# USB_Block.net
KiCad netlist of a schematic drawn in Altium Designer
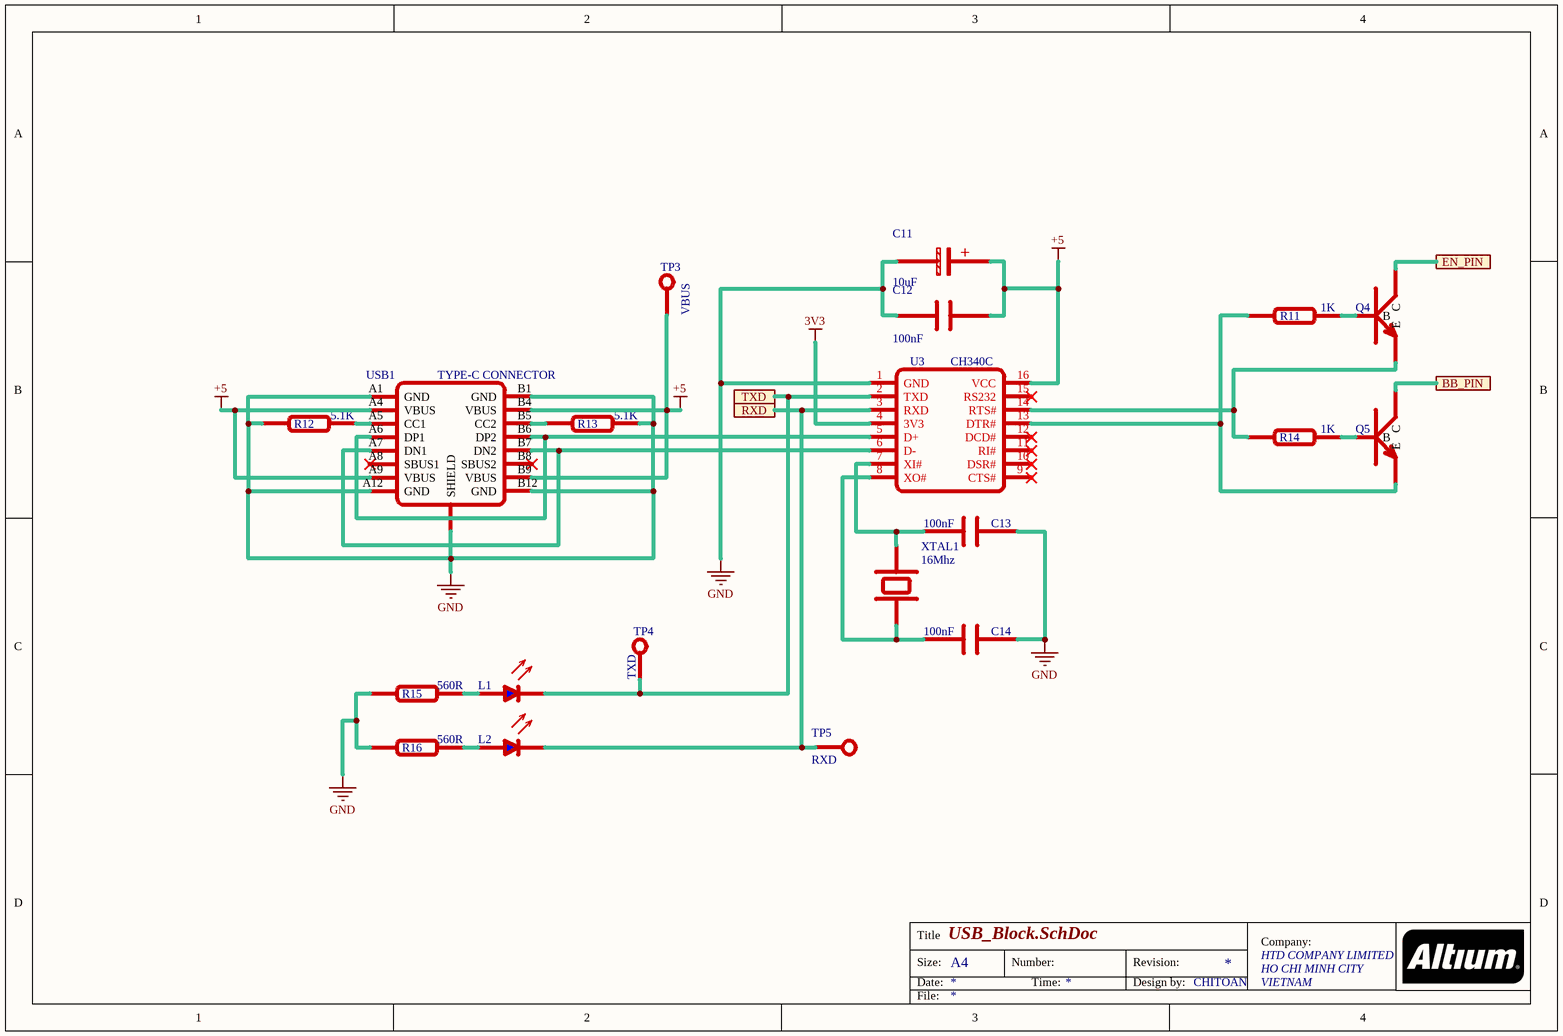
[diagram p0: USB_Block.SchDoc]

(export (version "E")
  (design (tool "Eeschema 10.0.6"))
  (components
    (comp (ref "C11")
      (value "10uF")
      (footprint "CAP-AL-4x5.4")
      (description "Aluminum Capacitor")
      (libsource (lib "CTAI-Library") (part "CAP-ALU"))
    )
    (comp (ref "C12")
      (value "100nF")
      (footprint "C0805")
      (description "Ceramic Capacitor")
      (libsource (lib "CTAI-Library") (part "CAP-CER"))
    )
    (comp (ref "C13")
      (value "100nF")
      (footprint "C0805")
      (description "Ceramic Capacitor")
      (libsource (lib "CTAI-Library") (part "CAP-CER"))
    )
    (comp (ref "C14")
      (value "100nF")
      (footprint "C0805")
      (description "Ceramic Capacitor")
      (libsource (lib "CTAI-Library") (part "CAP-CER"))
    )
    (comp (ref "L1")
      (value "LED-BLUE")
      (footprint "LED-0603-BLUE")
      (description "Blue Light Emiter Diode")
      (libsource (lib "CTAI-Library") (part "LED-Blue"))
    )
    (comp (ref "L2")
      (value "LED-BLUE")
      (footprint "LED-0603-BLUE")
      (description "Blue Light Emiter Diode")
      (libsource (lib "CTAI-Library") (part "LED-Blue"))
    )
    (comp (ref "Q4")
      (value "S8050")
      (footprint "SOT-23")
      (description "NPN Transistors 0.5A Collector to Emitter 25V")
      (libsource (lib "CTAI-Library") (part "S8050"))
    )
    (comp (ref "Q5")
      (value "S8050")
      (footprint "SOT-23")
      (description "NPN Transistors 0.5A Collector to Emitter 25V")
      (libsource (lib "CTAI-Library") (part "S8050"))
    )
    (comp (ref "R11")
      (value "1K")
      (footprint "R0603")
      (description "Resistor")
      (libsource (lib "CTAI-Library") (part "Resistor"))
    )
    (comp (ref "R12")
      (value "5.1K")
      (footprint "R0603")
      (description "Resistor")
      (libsource (lib "CTAI-Library") (part "Resistor"))
    )
    (comp (ref "R13")
      (value "5.1K")
      (footprint "R0603")
      (description "Resistor")
      (libsource (lib "CTAI-Library") (part "Resistor"))
    )
    (comp (ref "R14")
      (value "1K")
      (footprint "R0603")
      (description "Resistor")
      (libsource (lib "CTAI-Library") (part "Resistor"))
    )
    (comp (ref "R15")
      (value "560R")
      (footprint "R0603")
      (description "Resistor")
      (libsource (lib "CTAI-Library") (part "Resistor"))
    )
    (comp (ref "R16")
      (value "560R")
      (footprint "R0603")
      (description "Resistor")
      (libsource (lib "CTAI-Library") (part "Resistor"))
    )
    (comp (ref "TP3")
      (value "VBUS")
      (footprint "Test Point")
      (description "Test Point")
      (libsource (lib "CTAI-Library") (part "TestPoint"))
    )
    (comp (ref "TP4")
      (value "TXD")
      (footprint "Test Point")
      (description "Test Point")
      (libsource (lib "CTAI-Library") (part "TestPoint"))
    )
    (comp (ref "TP5")
      (value "RXD")
      (footprint "Test Point")
      (description "Test Point")
      (libsource (lib "CTAI-Library") (part "TestPoint"))
    )
    (comp (ref "U3")
      (value "CH340C")
      (footprint "SOP-16")
      (description "USB to UART bridge\r\nCH340-G-C-B")
      (libsource (lib "CTAI-Library") (part "CH340-16P"))
    )
    (comp (ref "USB1")
      (value "TYPE-C CONNECTOR")
      (footprint "USB-C-H-K-16P")
      (description "16P USB TYPE-C CONNECTOR")
      (libsource (lib "CTAI-Library") (part "USB-C-F-16P"))
    )
    (comp (ref "XTAL1")
      (value "16Mhz")
      (footprint "Crystal 5032")
      (description "Crystall 3Pin Capacitor Intergrated")
      (libsource (lib "CTAI-Library") (part "CRYSTAL-4P"))
    )
  )
  (nets
    (net (code "1") (name "+5") (class "Default")
      (node (ref "C11") (pin "1") (pintype "passive"))
      (node (ref "C12") (pin "2") (pintype "passive"))
      (node (ref "TP3") (pin "1") (pinfunction "1_1") (pintype "passive"))
      (node (ref "U3") (pin "16") (pinfunction "VCC_16") (pintype "passive"))
      (node (ref "USB1") (pin "A4") (pinfunction "VBUS_A4") (pintype "passive"))
      (node (ref "USB1") (pin "A9") (pinfunction "VBUS_A9") (pintype "passive"))
      (node (ref "USB1") (pin "B4") (pinfunction "VBUS_B4") (pintype "passive"))
      (node (ref "USB1") (pin "B9") (pinfunction "VBUS_B9") (pintype "passive"))
    )
    (net (code "2") (name "/BB_PIN") (class "Default")
      (node (ref "Q5") (pin "3") (pinfunction "C_3") (pintype "passive"))
    )
    (net (code "3") (name "/EN_PIN") (class "Default")
      (node (ref "Q4") (pin "3") (pinfunction "C_3") (pintype "passive"))
    )
    (net (code "4") (name "/RXD") (class "Default")
      (node (ref "L2") (pin "2") (pinfunction "K_2") (pintype "passive"))
      (node (ref "TP5") (pin "1") (pinfunction "1_1") (pintype "passive"))
      (node (ref "U3") (pin "3") (pinfunction "RXD_3") (pintype "passive"))
    )
    (net (code "5") (name "/TXD") (class "Default")
      (node (ref "L1") (pin "2") (pinfunction "K_2") (pintype "passive"))
      (node (ref "TP4") (pin "1") (pinfunction "1_1") (pintype "passive"))
      (node (ref "U3") (pin "2") (pinfunction "TXD_2") (pintype "passive"))
    )
    (net (code "6") (name "3V3") (class "Default")
      (node (ref "U3") (pin "4") (pinfunction "3V3_4") (pintype "passive"))
    )
    (net (code "7") (name "GND") (class "Default")
      (node (ref "C11") (pin "2") (pintype "passive"))
      (node (ref "C12") (pin "1") (pintype "passive"))
      (node (ref "C13") (pin "1") (pintype "passive"))
      (node (ref "C14") (pin "1") (pintype "passive"))
      (node (ref "R12") (pin "2") (pinfunction "2_2") (pintype "passive"))
      (node (ref "R13") (pin "1") (pinfunction "1_1") (pintype "passive"))
      (node (ref "R15") (pin "1") (pinfunction "1_1") (pintype "passive"))
      (node (ref "R16") (pin "1") (pinfunction "1_1") (pintype "passive"))
      (node (ref "U3") (pin "1") (pinfunction "GND_1") (pintype "passive"))
      (node (ref "USB1") (pin "0") (pinfunction "SHIELD_0") (pintype "passive"))
      (node (ref "USB1") (pin "A1") (pinfunction "GND_A1") (pintype "passive"))
      (node (ref "USB1") (pin "A12") (pinfunction "GND_A12") (pintype "passive"))
      (node (ref "USB1") (pin "B1") (pinfunction "GND_B1") (pintype "passive"))
      (node (ref "USB1") (pin "B12") (pinfunction "GND_B12") (pintype "passive"))
    )
    (net (code "8") (name "Net-(L1-A)") (class "Default")
      (node (ref "L1") (pin "1") (pinfunction "A_1") (pintype "passive"))
      (node (ref "R15") (pin "2") (pinfunction "2_2") (pintype "passive"))
    )
    (net (code "9") (name "Net-(L2-A)") (class "Default")
      (node (ref "L2") (pin "1") (pinfunction "A_1") (pintype "passive"))
      (node (ref "R16") (pin "2") (pinfunction "2_2") (pintype "passive"))
    )
    (net (code "10") (name "Net-(Q4-B)") (class "Default")
      (node (ref "Q4") (pin "1") (pinfunction "B_1") (pintype "passive"))
      (node (ref "R11") (pin "2") (pinfunction "2_2") (pintype "passive"))
    )
    (net (code "11") (name "Net-(Q4-E)") (class "Default")
      (node (ref "Q4") (pin "2") (pinfunction "E_2") (pintype "passive"))
      (node (ref "R14") (pin "1") (pinfunction "1_1") (pintype "passive"))
      (node (ref "U3") (pin "14") (pinfunction "RTS#_14") (pintype "passive"))
    )
    (net (code "12") (name "Net-(Q5-B)") (class "Default")
      (node (ref "Q5") (pin "1") (pinfunction "B_1") (pintype "passive"))
      (node (ref "R14") (pin "2") (pinfunction "2_2") (pintype "passive"))
    )
    (net (code "13") (name "Net-(Q5-E)") (class "Default")
      (node (ref "Q5") (pin "2") (pinfunction "E_2") (pintype "passive"))
      (node (ref "R11") (pin "1") (pinfunction "1_1") (pintype "passive"))
      (node (ref "U3") (pin "13") (pinfunction "DTR#_13") (pintype "passive"))
    )
    (net (code "14") (name "Net-(U3-D+)") (class "Default")
      (node (ref "U3") (pin "5") (pinfunction "D+_5") (pintype "passive"))
      (node (ref "USB1") (pin "A6") (pinfunction "DP1_A6") (pintype "passive"))
      (node (ref "USB1") (pin "B6") (pinfunction "DP2_B6") (pintype "passive"))
    )
    (net (code "15") (name "Net-(U3-D-)") (class "Default")
      (node (ref "U3") (pin "6") (pinfunction "D-_6") (pintype "passive"))
      (node (ref "USB1") (pin "A7") (pinfunction "DN1_A7") (pintype "passive"))
      (node (ref "USB1") (pin "B7") (pinfunction "DN2_B7") (pintype "passive"))
    )
    (net (code "16") (name "Net-(U3-XI#)") (class "Default")
      (node (ref "C13") (pin "2") (pintype "passive"))
      (node (ref "U3") (pin "7") (pinfunction "XI#_7") (pintype "passive"))
      (node (ref "XTAL1") (pin "1") (pintype "passive"))
    )
    (net (code "17") (name "Net-(U3-XO#)") (class "Default")
      (node (ref "C14") (pin "2") (pintype "passive"))
      (node (ref "U3") (pin "8") (pinfunction "XO#_8") (pintype "passive"))
      (node (ref "XTAL1") (pin "3") (pintype "passive"))
    )
    (net (code "18") (name "Net-(USB1-CC1)") (class "Default")
      (node (ref "R12") (pin "1") (pinfunction "1_1") (pintype "passive"))
      (node (ref "USB1") (pin "A5") (pinfunction "CC1_A5") (pintype "passive"))
    )
    (net (code "19") (name "Net-(USB1-CC2)") (class "Default")
      (node (ref "R13") (pin "2") (pinfunction "2_2") (pintype "passive"))
      (node (ref "USB1") (pin "B5") (pinfunction "CC2_B5") (pintype "passive"))
    )
    (net (code "20") (name "unconnected-(U3-CTS#-Pad9)") (class "Default")
      (node (ref "U3") (pin "9") (pinfunction "CTS#_9") (pintype "passive+no_connect"))
    )
    (net (code "21") (name "unconnected-(U3-DCD#-Pad12)") (class "Default")
      (node (ref "U3") (pin "12") (pinfunction "DCD#_12") (pintype "passive+no_connect"))
    )
    (net (code "22") (name "unconnected-(U3-DSR#-Pad10)") (class "Default")
      (node (ref "U3") (pin "10") (pinfunction "DSR#_10") (pintype "passive+no_connect"))
    )
    (net (code "23") (name "unconnected-(U3-RI#-Pad11)") (class "Default")
      (node (ref "U3") (pin "11") (pinfunction "RI#_11") (pintype "passive+no_connect"))
    )
    (net (code "24") (name "unconnected-(U3-RS232-Pad15)") (class "Default")
      (node (ref "U3") (pin "15") (pinfunction "RS232_15") (pintype "passive+no_connect"))
    )
    (net (code "25") (name "unconnected-(USB1-SBUS1-PadA8)") (class "Default")
      (node (ref "USB1") (pin "A8") (pinfunction "SBUS1_A8") (pintype "passive+no_connect"))
    )
    (net (code "26") (name "unconnected-(USB1-SBUS2-PadB8)") (class "Default")
      (node (ref "USB1") (pin "B8") (pinfunction "SBUS2_B8") (pintype "passive+no_connect"))
    )
    (net (code "27") (name "unconnected-(XTAL1-Pad2)") (class "Default")
      (node (ref "XTAL1") (pin "2") (pintype "passive"))
    )
    (net (code "28") (name "unconnected-(XTAL1-Pad4)") (class "Default")
      (node (ref "XTAL1") (pin "4") (pintype "passive"))
    )
  )
)
